# Croduino_Nova_v1_2.net
KiCad netlist of a schematic drawn in EAGLE
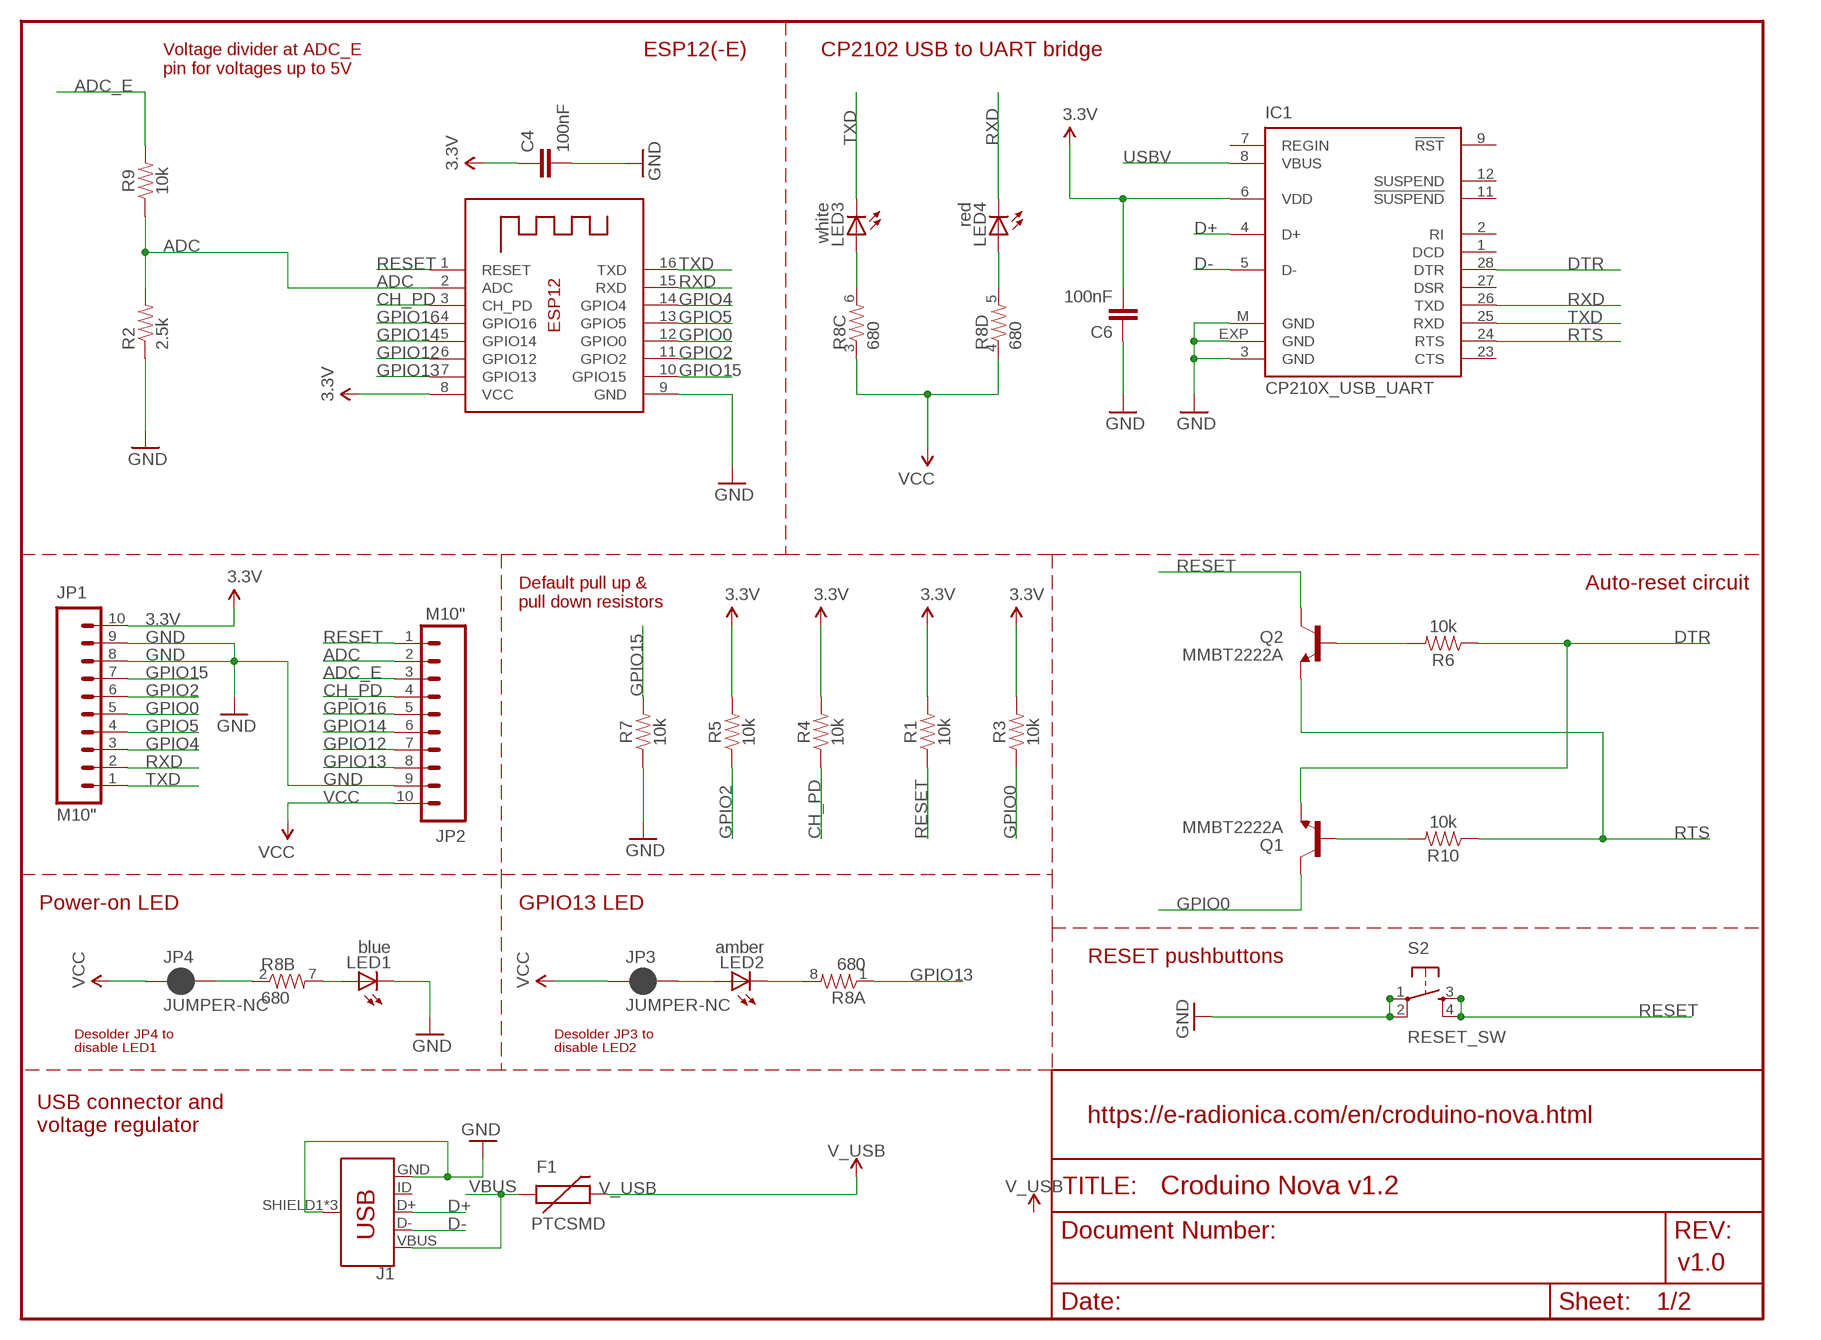
[diagram p0: schematic, sheet 1]
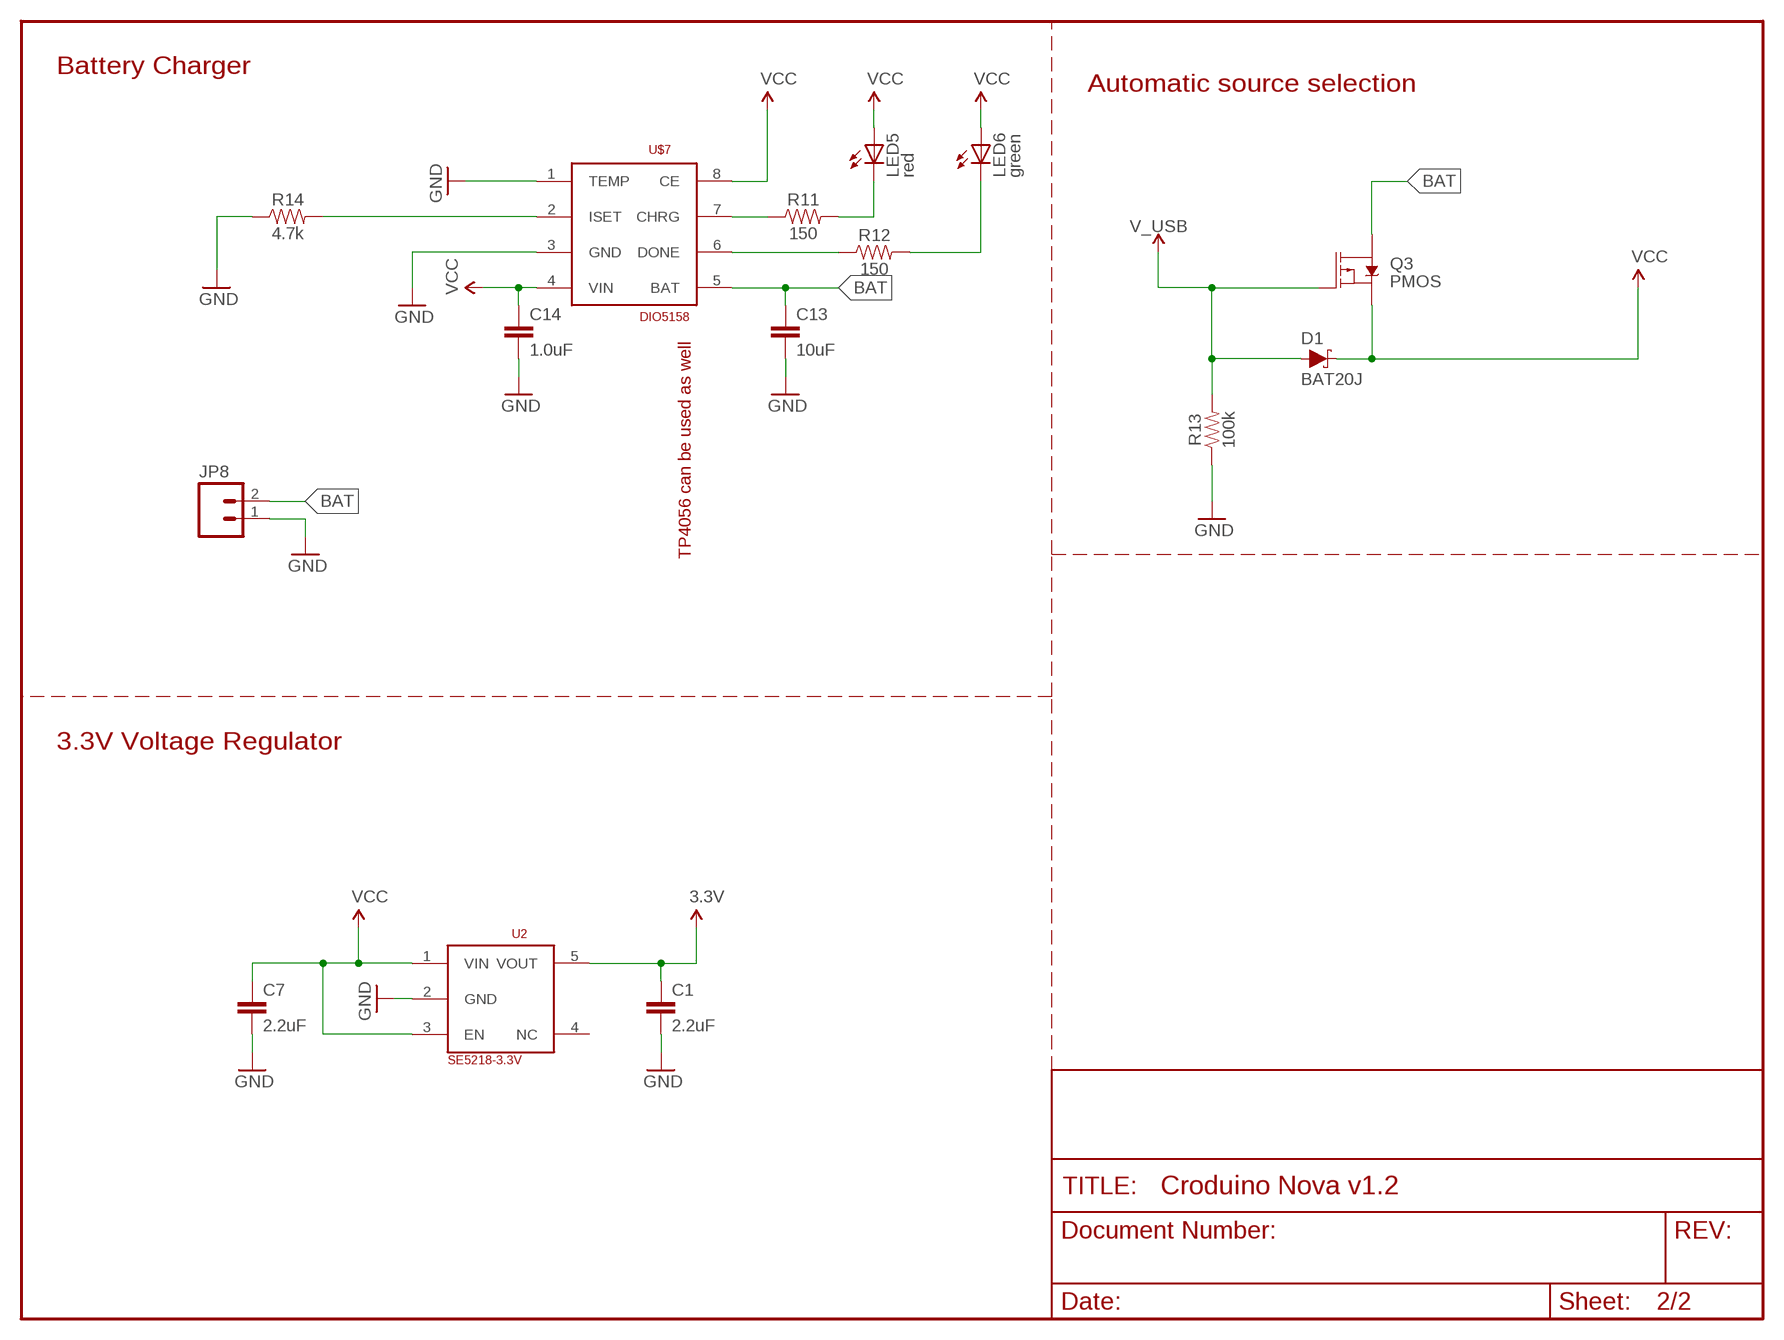
[diagram p1: schematic, sheet 2]

(export (version "E")
  (design (tool "Eeschema 10.0.6"))
  (components
    (comp (ref "C4")
      (value "100nF")
      (footprint "eagle-import:0603-CAP")
      (libsource (lib "eagle-import") (part "CAP0603-CAP"))
    )
    (comp (ref "C6")
      (value "100nF")
      (footprint "eagle-import:0603-CAP")
      (libsource (lib "eagle-import") (part "CAP0603-CAP"))
    )
    (comp (ref "F1")
      (value "PTCSMD")
      (footprint "eagle-import:PTC-1206")
      (libsource (lib "eagle-import") (part "PTCSMD"))
    )
    (comp (ref "IC1")
      (value "CP210X_USB_UART")
      (footprint "eagle-import:MLP28")
      (libsource (lib "eagle-import") (part "CP210X_USB_UART"))
    )
    (comp (ref "J1")
      (value "USB_MICRO-BREDUCED_PASTE")
      (footprint "eagle-import:USB-B-MICRO-SMD_RED_PASTE")
      (libsource (lib "eagle-import") (part "USB_MICRO-BREDUCED_PASTE"))
    )
    (comp (ref "JP1")
      (value "M10\"")
      (footprint "eagle-import:1X10")
      (libsource (lib "eagle-import") (part "M10{dblquote}"))
    )
    (comp (ref "JP2")
      (value "M10\"")
      (footprint "eagle-import:1X10")
      (libsource (lib "eagle-import") (part "M10{dblquote}"))
    )
    (comp (ref "JP3")
      (value "JUMPER-NC")
      (footprint "eagle-import:SMT-JUMPER_2_NC_PASTE_NO-SILK")
      (libsource (lib "eagle-import") (part "JUMPER-SMT_2_NC_PASTE_NO-SILK"))
    )
    (comp (ref "JP4")
      (value "JUMPER-NC")
      (footprint "eagle-import:SMT-JUMPER_2_NC_PASTE_NO-SILK")
      (libsource (lib "eagle-import") (part "JUMPER-SMT_2_NC_PASTE_NO-SILK"))
    )
    (comp (ref "LED1")
      (value "blue")
      (footprint "eagle-import:CHIP-LED0805")
      (libsource (lib "eagle-import") (part "LEDCHIP-LED0805"))
    )
    (comp (ref "LED2")
      (value "amber")
      (footprint "eagle-import:CHIP-LED0805")
      (libsource (lib "eagle-import") (part "LEDCHIP-LED0805"))
    )
    (comp (ref "LED3")
      (value "white")
      (footprint "eagle-import:CHIP-LED0805")
      (libsource (lib "eagle-import") (part "LEDCHIP-LED0805"))
    )
    (comp (ref "LED4")
      (value "red")
      (footprint "eagle-import:CHIP-LED0805")
      (libsource (lib "eagle-import") (part "LEDCHIP-LED0805"))
    )
    (comp (ref "Q1")
      (value "MMBT2222A")
      (footprint "eagle-import:SOT23-3")
      (libsource (lib "eagle-import") (part "TRANSISTOR_NPNSOT23-3"))
    )
    (comp (ref "Q2")
      (value "MMBT2222A")
      (footprint "eagle-import:SOT23-3")
      (libsource (lib "eagle-import") (part "TRANSISTOR_NPNSOT23-3"))
    )
    (comp (ref "R1")
      (value "10k")
      (footprint "eagle-import:0603")
      (libsource (lib "eagle-import") (part "10KOHM-0603-1/10W-1%"))
    )
    (comp (ref "R2")
      (value "2.5k")
      (footprint "eagle-import:0603-RES")
      (libsource (lib "eagle-import") (part "RESISTOR0603-RES"))
    )
    (comp (ref "R3")
      (value "10k")
      (footprint "eagle-import:0603")
      (libsource (lib "eagle-import") (part "10KOHM-0603-1/10W-1%"))
    )
    (comp (ref "R4")
      (value "10k")
      (footprint "eagle-import:0603")
      (libsource (lib "eagle-import") (part "10KOHM-0603-1/10W-1%"))
    )
    (comp (ref "R5")
      (value "10k")
      (footprint "eagle-import:0603")
      (libsource (lib "eagle-import") (part "10KOHM-0603-1/10W-1%"))
    )
    (comp (ref "R6")
      (value "10k")
      (footprint "eagle-import:0603")
      (libsource (lib "eagle-import") (part "10KOHM-0603-1/10W-1%"))
    )
    (comp (ref "R7")
      (value "10k")
      (footprint "eagle-import:0603")
      (libsource (lib "eagle-import") (part "10KOHM-0603-1/10W-1%"))
    )
    (comp (ref "R8")
      (value "680")
      (footprint "eagle-import:0603-ARV")
      (libsource (lib "eagle-import") (part "RESISTOR-ARRAY0603-ARV"))
    )
    (comp (ref "R9")
      (value "10k")
      (footprint "eagle-import:0603")
      (libsource (lib "eagle-import") (part "10KOHM-0603-1/10W-1%"))
    )
    (comp (ref "R10")
      (value "10k")
      (footprint "eagle-import:0603")
      (libsource (lib "eagle-import") (part "10KOHM-0603-1/10W-1%"))
    )
    (comp (ref "S2")
      (value "RESET_SW")
      (footprint "eagle-import:TACTILE_SWITCH_SMD")
      (libsource (lib "eagle-import") (part "TAC_SWITCHSMD"))
    )
    (comp (ref "X1")
      (value "ESP8266-12")
      (footprint "eagle-import:ESP-12")
      (libsource (lib "eagle-import") (part "ESP-12"))
    )
    (comp (ref "C1")
      (value "2.2uF")
      (footprint "eagle-import:0603")
      (libsource (lib "eagle-import") (part "2.2UF-0603-10V-20%"))
    )
    (comp (ref "C7")
      (value "2.2uF")
      (footprint "eagle-import:0603")
      (libsource (lib "eagle-import") (part "2.2UF-0603-10V-20%"))
    )
    (comp (ref "C13")
      (value "10uF")
      (footprint "eagle-import:1206")
      (libsource (lib "eagle-import") (part "10UF-1206-6.3V-20%"))
    )
    (comp (ref "C14")
      (value "1.0uF")
      (footprint "eagle-import:0603")
      (libsource (lib "eagle-import") (part "1.0UF-0603-16V-10%"))
    )
    (comp (ref "D1")
      (value "BAT20J")
      (footprint "eagle-import:SOD-323")
      (libsource (lib "eagle-import") (part "DIODE-SCHOTTKY-BAT20J"))
    )
    (comp (ref "JP8")
      (value "M02-JST-2MM-SMT")
      (footprint "eagle-import:JST-2-SMD")
      (libsource (lib "eagle-import") (part "M02-JST-2MM-SMT"))
    )
    (comp (ref "LED5")
      (value "red")
      (footprint "eagle-import:CHIP-LED0805")
      (libsource (lib "eagle-import") (part "LEDCHIP-LED0805"))
    )
    (comp (ref "LED6")
      (value "green")
      (footprint "eagle-import:CHIP-LED0805")
      (libsource (lib "eagle-import") (part "LEDCHIP-LED0805"))
    )
    (comp (ref "Q3")
      (value "PMOS")
      (footprint "eagle-import:SOT23-3")
      (libsource (lib "eagle-import") (part "MOSFET_PCH-IRLML2244"))
    )
    (comp (ref "R11")
      (value "150")
      (footprint "eagle-import:0603")
      (libsource (lib "eagle-import") (part "150OHM-0603-1/10W-1%"))
    )
    (comp (ref "R12")
      (value "150")
      (footprint "eagle-import:0603")
      (libsource (lib "eagle-import") (part "150OHM-0603-1/10W-1%"))
    )
    (comp (ref "R13")
      (value "100k")
      (footprint "eagle-import:0603")
      (libsource (lib "eagle-import") (part "100KOHM-0603-1/10W-1%"))
    )
    (comp (ref "R14")
      (value "4.7k")
      (footprint "eagle-import:0603")
      (libsource (lib "eagle-import") (part "4.7KOHM-0603-1/10W-1%"))
    )
    (comp (ref "U$7")
      (value "DIO5158")
      (footprint "eagle-import:SOIC-8")
      (libsource (lib "eagle-import") (part "DIO5158"))
    )
    (comp (ref "U2")
      (value "SE5218-3.3V")
      (footprint "eagle-import:SOT23-5")
      (libsource (lib "eagle-import") (part "SE5218"))
    )
  )
  (nets
    (net (code "1") (name "3.3V") (class "Default")
      (node (ref "C1") (pin "1") (pinfunction "1_1") (pintype "passive"))
      (node (ref "C4") (pin "1") (pinfunction "1_1") (pintype "passive"))
      (node (ref "C6") (pin "2") (pinfunction "2_2") (pintype "passive"))
      (node (ref "IC1") (pin "6") (pinfunction "VDD_6") (pintype "power_in"))
      (node (ref "JP1") (pin "10") (pinfunction "10_10") (pintype "passive"))
      (node (ref "R1") (pin "2") (pinfunction "2_2") (pintype "passive"))
      (node (ref "R3") (pin "2") (pinfunction "2_2") (pintype "passive"))
      (node (ref "R4") (pin "2") (pinfunction "2_2") (pintype "passive"))
      (node (ref "R5") (pin "2") (pinfunction "2_2") (pintype "passive"))
      (node (ref "U2") (pin "5") (pinfunction "VOUT_5") (pintype "bidirectional"))
      (node (ref "X1") (pin "8") (pinfunction "VCC_8") (pintype "power_in"))
    )
    (net (code "2") (name "ADC") (class "Default")
      (node (ref "JP2") (pin "2") (pinfunction "2_2") (pintype "passive"))
      (node (ref "R2") (pin "2") (pinfunction "2_2") (pintype "passive"))
      (node (ref "R9") (pin "1") (pinfunction "1_1") (pintype "passive"))
      (node (ref "X1") (pin "2") (pinfunction "ADC_2") (pintype "passive"))
    )
    (net (code "3") (name "ADC_E") (class "Default")
      (node (ref "JP2") (pin "3") (pinfunction "3_3") (pintype "passive"))
      (node (ref "R9") (pin "2") (pinfunction "2_2") (pintype "passive"))
    )
    (net (code "4") (name "BAT") (class "Default")
      (node (ref "C13") (pin "1") (pinfunction "1_1") (pintype "passive"))
      (node (ref "JP8") (pin "2") (pinfunction "2_2") (pintype "passive"))
      (node (ref "Q3") (pin "3") (pinfunction "D_3") (pintype "bidirectional"))
      (node (ref "U$7") (pin "5") (pinfunction "BAT_5") (pintype "bidirectional"))
    )
    (net (code "5") (name "CH_PD") (class "Default")
      (node (ref "JP2") (pin "4") (pinfunction "4_4") (pintype "passive"))
      (node (ref "R4") (pin "1") (pinfunction "1_1") (pintype "passive"))
      (node (ref "X1") (pin "3") (pinfunction "CH_PD_3") (pintype "input"))
    )
    (net (code "6") (name "D+") (class "Default")
      (node (ref "IC1") (pin "4") (pinfunction "D+_4") (pintype "bidirectional"))
      (node (ref "J1") (pin "D+") (pinfunction "D+_D+") (pintype "bidirectional"))
    )
    (net (code "7") (name "D-") (class "Default")
      (node (ref "IC1") (pin "5") (pinfunction "D-_5") (pintype "bidirectional"))
      (node (ref "J1") (pin "D-") (pinfunction "D-_D-") (pintype "bidirectional"))
    )
    (net (code "8") (name "DTR") (class "Default")
      (node (ref "IC1") (pin "28") (pinfunction "DTR_28") (pintype "output"))
      (node (ref "Q1") (pin "2") (pinfunction "E_2") (pintype "passive"))
      (node (ref "R6") (pin "1") (pinfunction "1_1") (pintype "passive"))
    )
    (net (code "9") (name "GND") (class "Default")
      (node (ref "C1") (pin "2") (pinfunction "2_2") (pintype "passive"))
      (node (ref "C13") (pin "2") (pinfunction "2_2") (pintype "passive"))
      (node (ref "C14") (pin "2") (pinfunction "2_2") (pintype "passive"))
      (node (ref "C4") (pin "2") (pinfunction "2_2") (pintype "passive"))
      (node (ref "C6") (pin "1") (pinfunction "1_1") (pintype "passive"))
      (node (ref "C7") (pin "2") (pinfunction "2_2") (pintype "passive"))
      (node (ref "IC1") (pin "3") (pinfunction "GND_3") (pintype "power_in"))
      (node (ref "IC1") (pin "EXP") (pinfunction "GND_EXP") (pintype "power_in"))
      (node (ref "IC1") (pin "M") (pinfunction "GND_M") (pintype "power_in"))
      (node (ref "J1") (pin "GND") (pinfunction "GND_GND") (pintype "power_in"))
      (node (ref "J1") (pin "SHIELD1") (pinfunction "SHIELD_SHIELD1") (pintype "bidirectional"))
      (node (ref "J1") (pin "SHIELD2") (pinfunction "SHIELD_SHIELD2") (pintype "bidirectional"))
      (node (ref "J1") (pin "SHIELD3") (pinfunction "SHIELD_SHIELD3") (pintype "bidirectional"))
      (node (ref "JP1") (pin "8") (pinfunction "8_8") (pintype "passive"))
      (node (ref "JP1") (pin "9") (pinfunction "9_9") (pintype "passive"))
      (node (ref "JP2") (pin "9") (pinfunction "9_9") (pintype "passive"))
      (node (ref "JP8") (pin "1") (pinfunction "1_1") (pintype "passive"))
      (node (ref "LED1") (pin "C") (pinfunction "C_C") (pintype "passive"))
      (node (ref "R13") (pin "1") (pinfunction "1_1") (pintype "passive"))
      (node (ref "R14") (pin "1") (pinfunction "1_1") (pintype "passive"))
      (node (ref "R2") (pin "1") (pinfunction "1_1") (pintype "passive"))
      (node (ref "R7") (pin "1") (pinfunction "1_1") (pintype "passive"))
      (node (ref "S2") (pin "1") (pinfunction "1_1") (pintype "passive"))
      (node (ref "S2") (pin "2") (pinfunction "2_2") (pintype "passive"))
      (node (ref "U$7") (pin "1") (pinfunction "TEMP_1") (pintype "bidirectional"))
      (node (ref "U$7") (pin "3") (pinfunction "GND_3") (pintype "bidirectional"))
      (node (ref "U2") (pin "2") (pinfunction "GND_2") (pintype "bidirectional"))
      (node (ref "X1") (pin "9") (pinfunction "GND_9") (pintype "power_in"))
    )
    (net (code "10") (name "GPIO0") (class "Default")
      (node (ref "JP1") (pin "5") (pinfunction "5_5") (pintype "passive"))
      (node (ref "Q1") (pin "3") (pinfunction "C_3") (pintype "passive"))
      (node (ref "R3") (pin "1") (pinfunction "1_1") (pintype "passive"))
      (node (ref "X1") (pin "12") (pinfunction "GPIO0_12") (pintype "bidirectional"))
    )
    (net (code "11") (name "GPIO2") (class "Default")
      (node (ref "JP1") (pin "6") (pinfunction "6_6") (pintype "passive"))
      (node (ref "R5") (pin "1") (pinfunction "1_1") (pintype "passive"))
      (node (ref "X1") (pin "11") (pinfunction "GPIO2_11") (pintype "bidirectional"))
    )
    (net (code "12") (name "GPIO4") (class "Default")
      (node (ref "JP1") (pin "3") (pinfunction "3_3") (pintype "passive"))
      (node (ref "X1") (pin "14") (pinfunction "GPIO4_14") (pintype "bidirectional"))
    )
    (net (code "13") (name "GPIO5") (class "Default")
      (node (ref "JP1") (pin "4") (pinfunction "4_4") (pintype "passive"))
      (node (ref "X1") (pin "13") (pinfunction "GPIO5_13") (pintype "bidirectional"))
    )
    (net (code "14") (name "GPIO12") (class "Default")
      (node (ref "JP2") (pin "7") (pinfunction "7_7") (pintype "passive"))
      (node (ref "X1") (pin "6") (pinfunction "GPIO12_6") (pintype "bidirectional"))
    )
    (net (code "15") (name "GPIO13") (class "Default")
      (node (ref "JP2") (pin "8") (pinfunction "8_8") (pintype "passive"))
      (node (ref "R8") (pin "1") (pinfunction "1_1") (pintype "passive"))
      (node (ref "X1") (pin "7") (pinfunction "GPIO13_7") (pintype "bidirectional"))
    )
    (net (code "16") (name "GPIO14") (class "Default")
      (node (ref "JP2") (pin "6") (pinfunction "6_6") (pintype "passive"))
      (node (ref "X1") (pin "5") (pinfunction "GPIO14_5") (pintype "bidirectional"))
    )
    (net (code "17") (name "GPIO15") (class "Default")
      (node (ref "JP1") (pin "7") (pinfunction "7_7") (pintype "passive"))
      (node (ref "R7") (pin "2") (pinfunction "2_2") (pintype "passive"))
      (node (ref "X1") (pin "10") (pinfunction "GPIO15_10") (pintype "bidirectional"))
    )
    (net (code "18") (name "GPIO16") (class "Default")
      (node (ref "JP2") (pin "5") (pinfunction "5_5") (pintype "passive"))
      (node (ref "X1") (pin "4") (pinfunction "GPIO16_4") (pintype "bidirectional"))
    )
    (net (code "19") (name "Net-(JP3-Pad2)") (class "Default")
      (node (ref "JP3") (pin "2") (pinfunction "2_2") (pintype "passive"))
      (node (ref "LED2") (pin "A") (pinfunction "A_A") (pintype "passive"))
    )
    (net (code "20") (name "Net-(LED5-PadC)") (class "Default")
      (node (ref "LED5") (pin "C") (pinfunction "C_C") (pintype "passive"))
      (node (ref "R11") (pin "2") (pinfunction "2_2") (pintype "passive"))
    )
    (net (code "21") (name "Net-(LED6-PadC)") (class "Default")
      (node (ref "LED6") (pin "C") (pinfunction "C_C") (pintype "passive"))
      (node (ref "R12") (pin "2") (pinfunction "2_2") (pintype "passive"))
    )
    (net (code "22") (name "Net-(Q1-B)") (class "Default")
      (node (ref "Q1") (pin "1") (pinfunction "B_1") (pintype "passive"))
      (node (ref "R10") (pin "2") (pinfunction "2_2") (pintype "passive"))
    )
    (net (code "23") (name "Net-(Q2-B)") (class "Default")
      (node (ref "Q2") (pin "1") (pinfunction "B_1") (pintype "passive"))
      (node (ref "R6") (pin "2") (pinfunction "2_2") (pintype "passive"))
    )
    (net (code "24") (name "Net-(R8A-2)") (class "Default")
      (node (ref "LED2") (pin "C") (pinfunction "C_C") (pintype "passive"))
      (node (ref "R8") (pin "8") (pinfunction "2_8") (pintype "passive"))
    )
    (net (code "25") (name "Net-(R8B-1)") (class "Default")
      (node (ref "JP4") (pin "2") (pinfunction "2_2") (pintype "passive"))
      (node (ref "R8") (pin "2") (pinfunction "1_2") (pintype "passive"))
    )
    (net (code "26") (name "Net-(R8B-2)") (class "Default")
      (node (ref "LED1") (pin "A") (pinfunction "A_A") (pintype "passive"))
      (node (ref "R8") (pin "7") (pinfunction "2_7") (pintype "passive"))
    )
    (net (code "27") (name "Net-(R8C-2)") (class "Default")
      (node (ref "LED3") (pin "A") (pinfunction "A_A") (pintype "passive"))
      (node (ref "R8") (pin "6") (pinfunction "2_6") (pintype "passive"))
    )
    (net (code "28") (name "Net-(R8D-2)") (class "Default")
      (node (ref "LED4") (pin "A") (pinfunction "A_A") (pintype "passive"))
      (node (ref "R8") (pin "5") (pinfunction "2_5") (pintype "passive"))
    )
    (net (code "29") (name "Net-(U$7-CHRG)") (class "Default")
      (node (ref "R11") (pin "1") (pinfunction "1_1") (pintype "passive"))
      (node (ref "U$7") (pin "7") (pinfunction "CHRG_7") (pintype "bidirectional"))
    )
    (net (code "30") (name "Net-(U$7-DONE)") (class "Default")
      (node (ref "R12") (pin "1") (pinfunction "1_1") (pintype "passive"))
      (node (ref "U$7") (pin "6") (pinfunction "DONE_6") (pintype "bidirectional"))
    )
    (net (code "31") (name "Net-(U$7-ISET)") (class "Default")
      (node (ref "R14") (pin "2") (pinfunction "2_2") (pintype "passive"))
      (node (ref "U$7") (pin "2") (pinfunction "ISET_2") (pintype "bidirectional"))
    )
    (net (code "32") (name "RESET") (class "Default")
      (node (ref "JP2") (pin "1") (pinfunction "1_1") (pintype "passive"))
      (node (ref "Q2") (pin "3") (pinfunction "C_3") (pintype "passive"))
      (node (ref "R1") (pin "1") (pinfunction "1_1") (pintype "passive"))
      (node (ref "S2") (pin "3") (pinfunction "3_3") (pintype "passive"))
      (node (ref "S2") (pin "4") (pinfunction "4_4") (pintype "passive"))
      (node (ref "X1") (pin "1") (pinfunction "RESET_1") (pintype "input"))
    )
    (net (code "33") (name "RTS") (class "Default")
      (node (ref "IC1") (pin "24") (pinfunction "RTS_24") (pintype "output"))
      (node (ref "Q2") (pin "2") (pinfunction "E_2") (pintype "passive"))
      (node (ref "R10") (pin "1") (pinfunction "1_1") (pintype "passive"))
    )
    (net (code "34") (name "RXD") (class "Default")
      (node (ref "IC1") (pin "26") (pinfunction "TXD_26") (pintype "output"))
      (node (ref "JP1") (pin "2") (pinfunction "2_2") (pintype "passive"))
      (node (ref "LED4") (pin "C") (pinfunction "C_C") (pintype "passive"))
      (node (ref "X1") (pin "15") (pinfunction "RXD_15") (pintype "input"))
    )
    (net (code "35") (name "TXD") (class "Default")
      (node (ref "IC1") (pin "25") (pinfunction "RXD_25") (pintype "input"))
      (node (ref "JP1") (pin "1") (pinfunction "1_1") (pintype "passive"))
      (node (ref "LED3") (pin "C") (pinfunction "C_C") (pintype "passive"))
      (node (ref "X1") (pin "16") (pinfunction "TXD_16") (pintype "output"))
    )
    (net (code "36") (name "USBV") (class "Default")
      (node (ref "IC1") (pin "8") (pinfunction "VBUS_8") (pintype "input"))
    )
    (net (code "37") (name "VBUS") (class "Default")
      (node (ref "F1") (pin "1") (pinfunction "1_1") (pintype "bidirectional"))
      (node (ref "J1") (pin "VBUS") (pinfunction "VBUS_VBUS") (pintype "power_in"))
    )
    (net (code "38") (name "VCC") (class "Default")
      (node (ref "C14") (pin "1") (pinfunction "1_1") (pintype "passive"))
      (node (ref "C7") (pin "1") (pinfunction "1_1") (pintype "passive"))
      (node (ref "D1") (pin "C") (pinfunction "C_C") (pintype "passive"))
      (node (ref "JP2") (pin "10") (pinfunction "10_10") (pintype "passive"))
      (node (ref "JP3") (pin "1") (pinfunction "1_1") (pintype "passive"))
      (node (ref "JP4") (pin "1") (pinfunction "1_1") (pintype "passive"))
      (node (ref "LED5") (pin "A") (pinfunction "A_A") (pintype "passive"))
      (node (ref "LED6") (pin "A") (pinfunction "A_A") (pintype "passive"))
      (node (ref "Q3") (pin "2") (pinfunction "S_2") (pintype "bidirectional"))
      (node (ref "R8") (pin "3") (pinfunction "1_3") (pintype "passive"))
      (node (ref "R8") (pin "4") (pinfunction "1_4") (pintype "passive"))
      (node (ref "U$7") (pin "4") (pinfunction "VIN_4") (pintype "bidirectional"))
      (node (ref "U$7") (pin "8") (pinfunction "CE_8") (pintype "bidirectional"))
      (node (ref "U2") (pin "1") (pinfunction "VIN_1") (pintype "bidirectional"))
      (node (ref "U2") (pin "3") (pinfunction "EN_3") (pintype "bidirectional"))
    )
    (net (code "39") (name "V_USB") (class "Default")
      (node (ref "D1") (pin "A") (pinfunction "A_A") (pintype "passive"))
      (node (ref "F1") (pin "2") (pinfunction "2_2") (pintype "bidirectional"))
      (node (ref "Q3") (pin "1") (pinfunction "G_1") (pintype "bidirectional"))
      (node (ref "R13") (pin "2") (pinfunction "2_2") (pintype "passive"))
    )
    (net (code "40") (name "unconnected-(IC1-CTS-Pad23)") (class "Default")
      (node (ref "IC1") (pin "23") (pinfunction "CTS_23") (pintype "input"))
    )
    (net (code "41") (name "unconnected-(IC1-DCD-Pad1)") (class "Default")
      (node (ref "IC1") (pin "1") (pinfunction "DCD_1") (pintype "input"))
    )
    (net (code "42") (name "unconnected-(IC1-DSR-Pad27)") (class "Default")
      (node (ref "IC1") (pin "27") (pinfunction "DSR_27") (pintype "input"))
    )
    (net (code "43") (name "unconnected-(IC1-REGIN-Pad7)") (class "Default")
      (node (ref "IC1") (pin "7") (pinfunction "REGIN_7") (pintype "passive"))
    )
    (net (code "44") (name "unconnected-(IC1-RI-Pad2)") (class "Default")
      (node (ref "IC1") (pin "2") (pinfunction "RI_2") (pintype "input"))
    )
    (net (code "45") (name "unconnected-(IC1-SUSPEND-Pad12)") (class "Default")
      (node (ref "IC1") (pin "12") (pinfunction "SUSPEND_12") (pintype "output"))
    )
    (net (code "46") (name "unconnected-(IC1-~{RST}-Pad9)") (class "Default")
      (node (ref "IC1") (pin "9") (pinfunction "~{RST}_9") (pintype "bidirectional"))
    )
    (net (code "47") (name "unconnected-(IC1-~{SUSPEND}-Pad11)") (class "Default")
      (node (ref "IC1") (pin "11") (pinfunction "~{SUSPEND}_11") (pintype "output"))
    )
    (net (code "48") (name "unconnected-(J1-PadID)") (class "Default")
      (node (ref "J1") (pin "ID") (pinfunction "ID_ID") (pintype "bidirectional"))
    )
    (net (code "49") (name "unconnected-(U2-NC-Pad4)") (class "Default")
      (node (ref "U2") (pin "4") (pinfunction "NC_4") (pintype "bidirectional"))
    )
  )
)
